# 5V_3V_LDO.net
KiCad netlist of a schematic drawn in Altium Designer
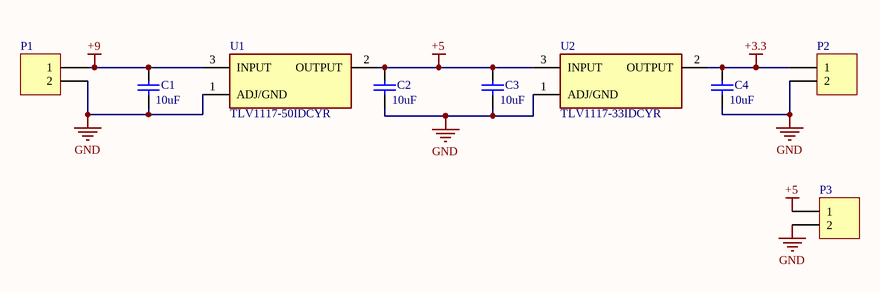
[diagram p0: 5V_3V_LDO.SchDoc]

(export (version "E")
  (design (tool "Eeschema 10.0.6"))
  (components
    (comp (ref "C1")
      (value "10uF")
      (footprint "0805 - Capacitor")
      (description "Nonpolarized Capacitor")
      (fields
        (field (name "MANUFACTURER") "Yageo")
        (field (name "MANUFACTURER PART NUMBER") "CC0805KKX5R8BB106")
      )
      (libsource (lib "General") (part "Capacitor - Nonpolarized"))
    )
    (comp (ref "C2")
      (value "10uF")
      (footprint "0805 - Capacitor")
      (description "Nonpolarized Capacitor")
      (fields
        (field (name "MANUFACTURER") "Yageo")
        (field (name "MANUFACTURER PART NUMBER") "CC0805KKX5R8BB106")
      )
      (libsource (lib "General") (part "Capacitor - Nonpolarized"))
    )
    (comp (ref "C3")
      (value "10uF")
      (footprint "0805 - Capacitor")
      (description "Nonpolarized Capacitor")
      (fields
        (field (name "MANUFACTURER") "Yageo")
        (field (name "MANUFACTURER PART NUMBER") "CC0805KKX5R8BB106")
      )
      (libsource (lib "General") (part "Capacitor - Nonpolarized"))
    )
    (comp (ref "C4")
      (value "10uF")
      (footprint "0805 - Capacitor")
      (description "Nonpolarized Capacitor")
      (fields
        (field (name "MANUFACTURER") "Yageo")
        (field (name "MANUFACTURER PART NUMBER") "CC0805KKX5R8BB106")
      )
      (libsource (lib "General") (part "Capacitor - Nonpolarized"))
    )
    (comp (ref "P1")
      (value "CUI_TB002-500-02")
      (footprint "CUI_TB002-500-02")
      (description "1x2 Screw Terminal Block")
      (fields
        (field (name "MANUFACTURER") "CUI Devices")
        (field (name "MANUFACTURER PART NUMBER") "TB002-500-02BE")
      )
      (libsource (lib "") (part "CUI_TB002-500-02_1"))
    )
    (comp (ref "P2")
      (value "CUI_TB002-500-02")
      (footprint "CUI_TB002-500-02")
      (description "1x2 Screw Terminal Block")
      (fields
        (field (name "MANUFACTURER") "CUI Devices")
        (field (name "MANUFACTURER PART NUMBER") "TB002-500-02BE")
      )
      (libsource (lib "GeneralConnectors") (part "CUI_TB002-500-02"))
    )
    (comp (ref "P3")
      (value "CUI_TB002-500-02")
      (footprint "CUI_TB002-500-02")
      (description "1x2 Screw Terminal Block")
      (fields
        (field (name "MANUFACTURER") "CUI Devices")
        (field (name "MANUFACTURER PART NUMBER") "TB002-500-02BE")
      )
      (libsource (lib "GeneralConnectors") (part "CUI_TB002-500-02"))
    )
    (comp (ref "U1")
      (value "TLV1117-50IDCYR")
      (footprint "TLV1117")
      (description "Linear Voltage Regulator IC 5V 800MA SOT223-4")
      (fields
        (field (name "MANUFACTURER") "Texas Instruments")
        (field (name "DIGIKEY PART NUMBER") "296-21115-1-ND")
      )
      (libsource (lib "GeneralComponents") (part "TLV1117-50IDCYR"))
    )
    (comp (ref "U2")
      (value "TLV1117-33IDCYR")
      (footprint "TLV1117")
      (description "Linear Voltage Regulator IC 3.3V 800MA SOT223-4")
      (fields
        (field (name "MANUFACTURER") "Texas Instruments")
        (field (name "DIGIKEY PART NUMBER") "296-21112-1-ND")
      )
      (libsource (lib "GeneralComponents") (part "TLV1117-33IDCYR"))
    )
  )
  (nets
    (net (code "1") (name "+3.3") (class "Default")
      (node (ref "C4") (pin "2") (pinfunction "2_2") (pintype "passive"))
      (node (ref "P2") (pin "1") (pinfunction "1_1") (pintype "passive"))
      (node (ref "U2") (pin "2") (pinfunction "OUTPUT_2") (pintype "passive"))
    )
    (net (code "2") (name "+5") (class "Default")
      (node (ref "C2") (pin "2") (pinfunction "2_2") (pintype "passive"))
      (node (ref "C3") (pin "2") (pinfunction "2_2") (pintype "passive"))
      (node (ref "P3") (pin "1") (pinfunction "1_1") (pintype "passive"))
      (node (ref "U1") (pin "2") (pinfunction "OUTPUT_2") (pintype "passive"))
      (node (ref "U2") (pin "3") (pinfunction "INPUT_3") (pintype "passive"))
    )
    (net (code "3") (name "+9") (class "Default")
      (node (ref "C1") (pin "2") (pinfunction "2_2") (pintype "passive"))
      (node (ref "P1") (pin "1") (pinfunction "1_1") (pintype "passive"))
      (node (ref "U1") (pin "3") (pinfunction "INPUT_3") (pintype "passive"))
    )
    (net (code "4") (name "GND") (class "Default")
      (node (ref "C1") (pin "1") (pinfunction "1_1") (pintype "passive"))
      (node (ref "C2") (pin "1") (pinfunction "1_1") (pintype "passive"))
      (node (ref "C3") (pin "1") (pinfunction "1_1") (pintype "passive"))
      (node (ref "C4") (pin "1") (pinfunction "1_1") (pintype "passive"))
      (node (ref "P1") (pin "2") (pinfunction "2_2") (pintype "passive"))
      (node (ref "P2") (pin "2") (pinfunction "2_2") (pintype "passive"))
      (node (ref "P3") (pin "2") (pinfunction "2_2") (pintype "passive"))
      (node (ref "U1") (pin "1") (pinfunction "ADJ/GND_1") (pintype "passive"))
      (node (ref "U2") (pin "1") (pinfunction "ADJ/GND_1") (pintype "passive"))
    )
  )
)
